# od-aws.net
KiCad netlist of a schematic drawn in EAGLE
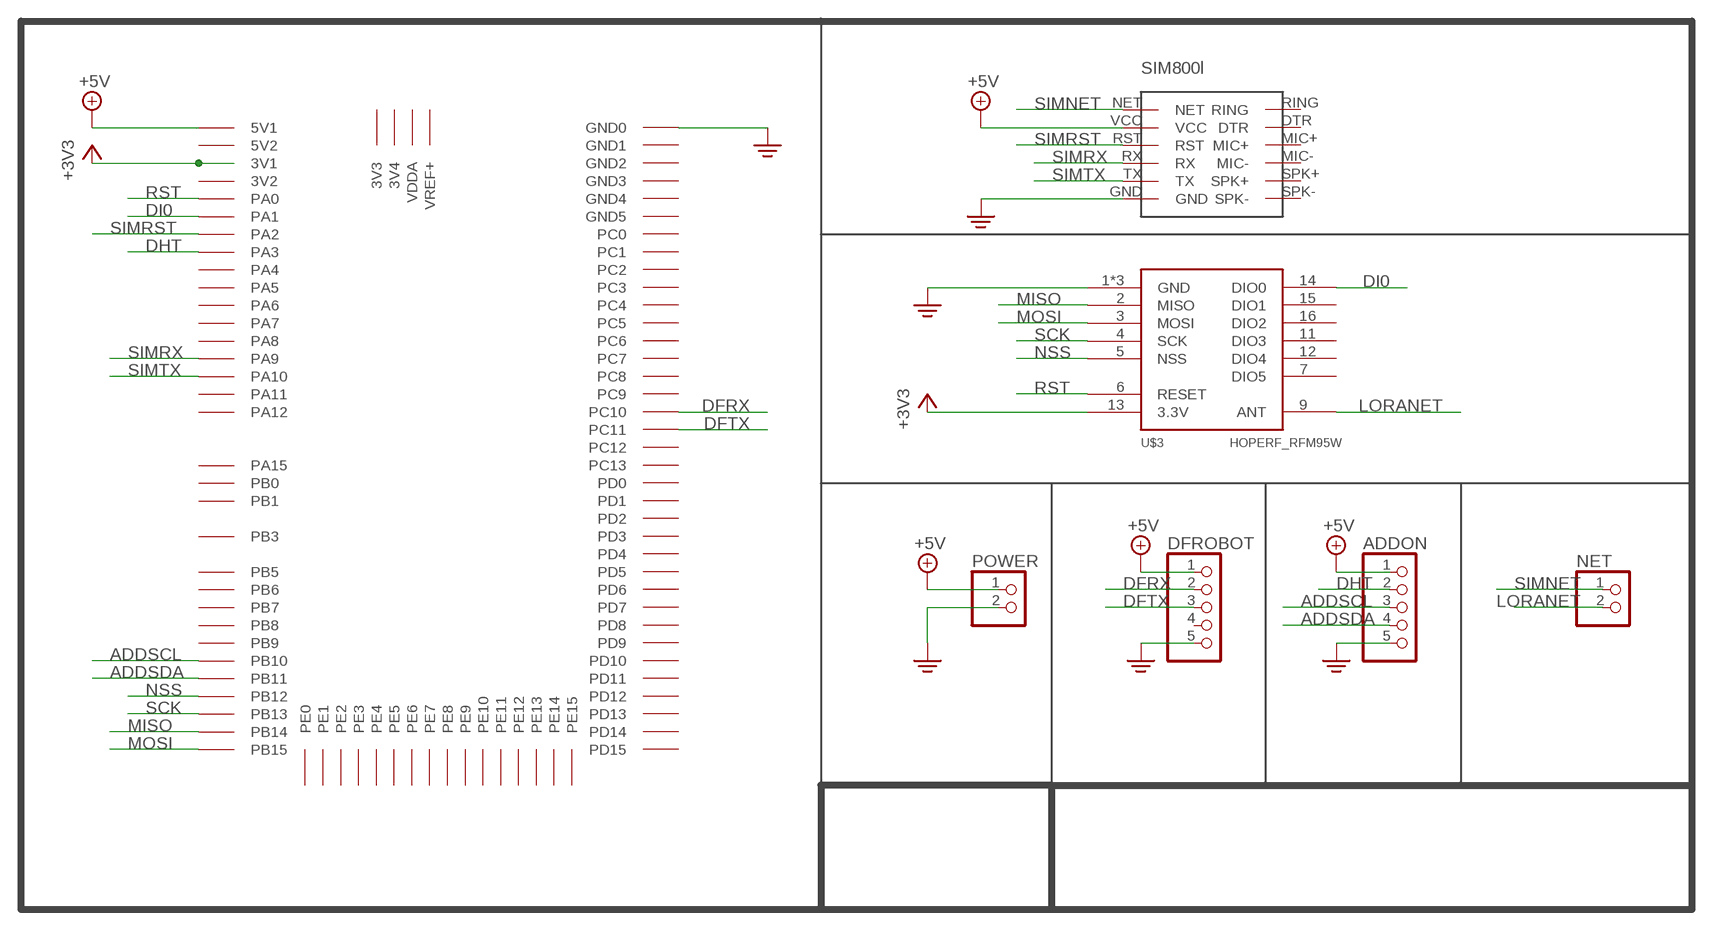
[diagram p0: schematic, sheet 1]

(export (version "E")
  (design (tool "Eeschema 10.0.6"))
  (components
    (comp (ref "ADDON")
      (value "PINHD-1X5/90")
      (footprint "eagle-import:1X05_90")
      (libsource (lib "eagle-import") (part "PINHD-1X5/90"))
    )
    (comp (ref "DFROBOT")
      (value "PINHD-1X5/90")
      (footprint "eagle-import:1X05_90")
      (libsource (lib "eagle-import") (part "PINHD-1X5/90"))
    )
    (comp (ref "NET")
      (value "PINHD-1X2/90")
      (footprint "eagle-import:1X02_90")
      (libsource (lib "eagle-import") (part "PINHD-1X2/90"))
    )
    (comp (ref "POWER")
      (value "PINHD-1X2/90")
      (footprint "eagle-import:1X02_90")
      (libsource (lib "eagle-import") (part "PINHD-1X2/90"))
    )
    (comp (ref "U$1")
      (value "STM32F407VGT6")
      (footprint "eagle-import:STM32F407VGT6")
      (libsource (lib "eagle-import") (part "STM32F407VGT6"))
    )
    (comp (ref "U$2")
      (value "SIM800L-V1")
      (footprint "eagle-import:SIM800L-V1")
      (libsource (lib "eagle-import") (part "SIM800L-V1"))
    )
    (comp (ref "U$3")
      (value "HOPERF_RFM95W")
      (footprint "eagle-import:HOPERF_RFM95W")
      (libsource (lib "eagle-import") (part "HOPERF_RFM95W"))
    )
  )
  (nets
    (net (code "1") (name "+3V3") (class "Default")
      (node (ref "U$1") (pin "3V31") (pinfunction "3V1_3V31") (pintype "bidirectional"))
      (node (ref "U$3") (pin "13") (pinfunction "3.3V_13") (pintype "power_in"))
    )
    (net (code "2") (name "+5V") (class "Default")
      (node (ref "ADDON") (pin "1") (pinfunction "1_1") (pintype "passive"))
      (node (ref "DFROBOT") (pin "1") (pinfunction "1_1") (pintype "passive"))
      (node (ref "POWER") (pin "1") (pinfunction "1_1") (pintype "passive"))
      (node (ref "U$1") (pin "5V1") (pinfunction "5V1_5V1") (pintype "bidirectional"))
      (node (ref "U$2") (pin "VCC") (pinfunction "VCC_VCC") (pintype "bidirectional"))
    )
    (net (code "3") (name "/ADDSCL") (class "Default")
      (node (ref "ADDON") (pin "3") (pinfunction "3_3") (pintype "passive"))
      (node (ref "U$1") (pin "PB10") (pinfunction "PB10_PB10") (pintype "bidirectional"))
    )
    (net (code "4") (name "/ADDSDA") (class "Default")
      (node (ref "ADDON") (pin "4") (pinfunction "4_4") (pintype "passive"))
      (node (ref "U$1") (pin "PB11") (pinfunction "PB11_PB11") (pintype "bidirectional"))
    )
    (net (code "5") (name "/DFRX") (class "Default")
      (node (ref "DFROBOT") (pin "2") (pinfunction "2_2") (pintype "passive"))
      (node (ref "U$1") (pin "PC10") (pinfunction "PC10_PC10") (pintype "bidirectional"))
    )
    (net (code "6") (name "/DFTX") (class "Default")
      (node (ref "DFROBOT") (pin "3") (pinfunction "3_3") (pintype "passive"))
      (node (ref "U$1") (pin "PC11") (pinfunction "PC11_PC11") (pintype "bidirectional"))
    )
    (net (code "7") (name "/DHT") (class "Default")
      (node (ref "ADDON") (pin "2") (pinfunction "2_2") (pintype "passive"))
      (node (ref "U$1") (pin "PA3") (pinfunction "PA3_PA3") (pintype "bidirectional"))
    )
    (net (code "8") (name "/DI0") (class "Default")
      (node (ref "U$1") (pin "PA1") (pinfunction "PA1_PA1") (pintype "bidirectional"))
      (node (ref "U$3") (pin "14") (pinfunction "DIO0_14") (pintype "bidirectional"))
    )
    (net (code "9") (name "/LORANET") (class "Default")
      (node (ref "NET") (pin "2") (pinfunction "2_2") (pintype "passive"))
      (node (ref "U$3") (pin "9") (pinfunction "ANT_9") (pintype "bidirectional"))
    )
    (net (code "10") (name "/MISO") (class "Default")
      (node (ref "U$1") (pin "PB14") (pinfunction "PB14_PB14") (pintype "bidirectional"))
      (node (ref "U$3") (pin "2") (pinfunction "MISO_2") (pintype "input"))
    )
    (net (code "11") (name "/MOSI") (class "Default")
      (node (ref "U$1") (pin "PB15") (pinfunction "PB15_PB15") (pintype "bidirectional"))
      (node (ref "U$3") (pin "3") (pinfunction "MOSI_3") (pintype "output"))
    )
    (net (code "12") (name "/NSS") (class "Default")
      (node (ref "U$1") (pin "PB12") (pinfunction "PB12_PB12") (pintype "bidirectional"))
      (node (ref "U$3") (pin "5") (pinfunction "NSS_5") (pintype "input"))
    )
    (net (code "13") (name "/RST") (class "Default")
      (node (ref "U$1") (pin "PA0") (pinfunction "PA0_PA0") (pintype "bidirectional"))
      (node (ref "U$3") (pin "6") (pinfunction "RESET_6") (pintype "bidirectional"))
    )
    (net (code "14") (name "/SCK") (class "Default")
      (node (ref "U$1") (pin "PB13") (pinfunction "PB13_PB13") (pintype "bidirectional"))
      (node (ref "U$3") (pin "4") (pinfunction "SCK_4") (pintype "input"))
    )
    (net (code "15") (name "/SIMNET") (class "Default")
      (node (ref "NET") (pin "1") (pinfunction "1_1") (pintype "passive"))
      (node (ref "U$2") (pin "NET") (pinfunction "NET_NET") (pintype "bidirectional"))
    )
    (net (code "16") (name "/SIMRST") (class "Default")
      (node (ref "U$1") (pin "PA2") (pinfunction "PA2_PA2") (pintype "bidirectional"))
      (node (ref "U$2") (pin "RST") (pinfunction "RST_RST") (pintype "bidirectional"))
    )
    (net (code "17") (name "/SIMRX") (class "Default")
      (node (ref "U$1") (pin "PA9") (pinfunction "PA9_PA9") (pintype "bidirectional"))
      (node (ref "U$2") (pin "RX") (pinfunction "RX_RX") (pintype "bidirectional"))
    )
    (net (code "18") (name "/SIMTX") (class "Default")
      (node (ref "U$1") (pin "PA10") (pinfunction "PA10_PA10") (pintype "bidirectional"))
      (node (ref "U$2") (pin "TX") (pinfunction "TX_TX") (pintype "bidirectional"))
    )
    (net (code "19") (name "PE") (class "Default")
      (node (ref "ADDON") (pin "5") (pinfunction "5_5") (pintype "passive"))
      (node (ref "DFROBOT") (pin "5") (pinfunction "5_5") (pintype "passive"))
      (node (ref "POWER") (pin "2") (pinfunction "2_2") (pintype "passive"))
      (node (ref "U$1") (pin "GND1") (pinfunction "GND0_GND1") (pintype "bidirectional"))
      (node (ref "U$2") (pin "GND") (pinfunction "GND_GND") (pintype "bidirectional"))
      (node (ref "U$3") (pin "1") (pinfunction "GND_1") (pintype "power_in"))
      (node (ref "U$3") (pin "10") (pinfunction "GND_10") (pintype "power_in"))
      (node (ref "U$3") (pin "8") (pinfunction "GND_8") (pintype "power_in"))
    )
    (net (code "20") (name "unconnected-(DFROBOT-Pad4)") (class "Default")
      (node (ref "DFROBOT") (pin "4") (pinfunction "4_4") (pintype "passive"))
    )
    (net (code "21") (name "unconnected-(U$1-3V2-Pad3V32)") (class "Default")
      (node (ref "U$1") (pin "3V32") (pinfunction "3V2_3V32") (pintype "bidirectional"))
    )
    (net (code "22") (name "unconnected-(U$1-3V3-Pad3V33)") (class "Default")
      (node (ref "U$1") (pin "3V33") (pinfunction "3V3_3V33") (pintype "bidirectional"))
    )
    (net (code "23") (name "unconnected-(U$1-3V4-Pad3V34)") (class "Default")
      (node (ref "U$1") (pin "3V34") (pinfunction "3V4_3V34") (pintype "bidirectional"))
    )
    (net (code "24") (name "unconnected-(U$1-GND1-PadGND2)") (class "Default")
      (node (ref "U$1") (pin "GND2") (pinfunction "GND1_GND2") (pintype "bidirectional"))
    )
    (net (code "25") (name "unconnected-(U$1-GND2-PadGND3)") (class "Default")
      (node (ref "U$1") (pin "GND3") (pinfunction "GND2_GND3") (pintype "bidirectional"))
    )
    (net (code "26") (name "unconnected-(U$1-GND3-PadGND4)") (class "Default")
      (node (ref "U$1") (pin "GND4") (pinfunction "GND3_GND4") (pintype "bidirectional"))
    )
    (net (code "27") (name "unconnected-(U$1-GND4-PadGND5)") (class "Default")
      (node (ref "U$1") (pin "GND5") (pinfunction "GND4_GND5") (pintype "bidirectional"))
    )
    (net (code "28") (name "unconnected-(U$1-GND5-PadGND7)") (class "Default")
      (node (ref "U$1") (pin "GND7") (pinfunction "GND5_GND7") (pintype "bidirectional"))
    )
    (net (code "29") (name "unconnected-(U$1-Pad5V2)") (class "Default")
      (node (ref "U$1") (pin "5V2") (pinfunction "5V2_5V2") (pintype "bidirectional"))
    )
    (net (code "30") (name "unconnected-(U$1-PadPA4)") (class "Default")
      (node (ref "U$1") (pin "PA4") (pinfunction "PA4_PA4") (pintype "bidirectional"))
    )
    (net (code "31") (name "unconnected-(U$1-PadPA5)") (class "Default")
      (node (ref "U$1") (pin "PA5") (pinfunction "PA5_PA5") (pintype "bidirectional"))
    )
    (net (code "32") (name "unconnected-(U$1-PadPA6)") (class "Default")
      (node (ref "U$1") (pin "PA6") (pinfunction "PA6_PA6") (pintype "bidirectional"))
    )
    (net (code "33") (name "unconnected-(U$1-PadPA7)") (class "Default")
      (node (ref "U$1") (pin "PA7") (pinfunction "PA7_PA7") (pintype "bidirectional"))
    )
    (net (code "34") (name "unconnected-(U$1-PadPA8)") (class "Default")
      (node (ref "U$1") (pin "PA8") (pinfunction "PA8_PA8") (pintype "bidirectional"))
    )
    (net (code "35") (name "unconnected-(U$1-PadPA11)") (class "Default")
      (node (ref "U$1") (pin "PA11") (pinfunction "PA11_PA11") (pintype "bidirectional"))
    )
    (net (code "36") (name "unconnected-(U$1-PadPA12)") (class "Default")
      (node (ref "U$1") (pin "PA12") (pinfunction "PA12_PA12") (pintype "bidirectional"))
    )
    (net (code "37") (name "unconnected-(U$1-PadPA15)") (class "Default")
      (node (ref "U$1") (pin "PA15") (pinfunction "PA15_PA15") (pintype "bidirectional"))
    )
    (net (code "38") (name "unconnected-(U$1-PadPB0)") (class "Default")
      (node (ref "U$1") (pin "PB0") (pinfunction "PB0_PB0") (pintype "bidirectional"))
    )
    (net (code "39") (name "unconnected-(U$1-PadPB1)") (class "Default")
      (node (ref "U$1") (pin "PB1") (pinfunction "PB1_PB1") (pintype "bidirectional"))
    )
    (net (code "40") (name "unconnected-(U$1-PadPB3)") (class "Default")
      (node (ref "U$1") (pin "PB3") (pinfunction "PB3_PB3") (pintype "bidirectional"))
    )
    (net (code "41") (name "unconnected-(U$1-PadPB5)") (class "Default")
      (node (ref "U$1") (pin "PB5") (pinfunction "PB5_PB5") (pintype "bidirectional"))
    )
    (net (code "42") (name "unconnected-(U$1-PadPB6)") (class "Default")
      (node (ref "U$1") (pin "PB6") (pinfunction "PB6_PB6") (pintype "bidirectional"))
    )
    (net (code "43") (name "unconnected-(U$1-PadPB7)") (class "Default")
      (node (ref "U$1") (pin "PB7") (pinfunction "PB7_PB7") (pintype "bidirectional"))
    )
    (net (code "44") (name "unconnected-(U$1-PadPB8)") (class "Default")
      (node (ref "U$1") (pin "PB8") (pinfunction "PB8_PB8") (pintype "bidirectional"))
    )
    (net (code "45") (name "unconnected-(U$1-PadPB9)") (class "Default")
      (node (ref "U$1") (pin "PB9") (pinfunction "PB9_PB9") (pintype "bidirectional"))
    )
    (net (code "46") (name "unconnected-(U$1-PadPC0)") (class "Default")
      (node (ref "U$1") (pin "PC0") (pinfunction "PC0_PC0") (pintype "bidirectional"))
    )
    (net (code "47") (name "unconnected-(U$1-PadPC1)") (class "Default")
      (node (ref "U$1") (pin "PC1") (pinfunction "PC1_PC1") (pintype "bidirectional"))
    )
    (net (code "48") (name "unconnected-(U$1-PadPC2)") (class "Default")
      (node (ref "U$1") (pin "PC2") (pinfunction "PC2_PC2") (pintype "bidirectional"))
    )
    (net (code "49") (name "unconnected-(U$1-PadPC3)") (class "Default")
      (node (ref "U$1") (pin "PC3") (pinfunction "PC3_PC3") (pintype "bidirectional"))
    )
    (net (code "50") (name "unconnected-(U$1-PadPC4)") (class "Default")
      (node (ref "U$1") (pin "PC4") (pinfunction "PC4_PC4") (pintype "bidirectional"))
    )
    (net (code "51") (name "unconnected-(U$1-PadPC5)") (class "Default")
      (node (ref "U$1") (pin "PC5") (pinfunction "PC5_PC5") (pintype "bidirectional"))
    )
    (net (code "52") (name "unconnected-(U$1-PadPC6)") (class "Default")
      (node (ref "U$1") (pin "PC6") (pinfunction "PC6_PC6") (pintype "bidirectional"))
    )
    (net (code "53") (name "unconnected-(U$1-PadPC7)") (class "Default")
      (node (ref "U$1") (pin "PC7") (pinfunction "PC7_PC7") (pintype "bidirectional"))
    )
    (net (code "54") (name "unconnected-(U$1-PadPC8)") (class "Default")
      (node (ref "U$1") (pin "PC8") (pinfunction "PC8_PC8") (pintype "bidirectional"))
    )
    (net (code "55") (name "unconnected-(U$1-PadPC9)") (class "Default")
      (node (ref "U$1") (pin "PC9") (pinfunction "PC9_PC9") (pintype "bidirectional"))
    )
    (net (code "56") (name "unconnected-(U$1-PadPC12)") (class "Default")
      (node (ref "U$1") (pin "PC12") (pinfunction "PC12_PC12") (pintype "bidirectional"))
    )
    (net (code "57") (name "unconnected-(U$1-PadPC13)") (class "Default")
      (node (ref "U$1") (pin "PC13") (pinfunction "PC13_PC13") (pintype "bidirectional"))
    )
    (net (code "58") (name "unconnected-(U$1-PadPD0)") (class "Default")
      (node (ref "U$1") (pin "PD0") (pinfunction "PD0_PD0") (pintype "bidirectional"))
    )
    (net (code "59") (name "unconnected-(U$1-PadPD1)") (class "Default")
      (node (ref "U$1") (pin "PD1") (pinfunction "PD1_PD1") (pintype "bidirectional"))
    )
    (net (code "60") (name "unconnected-(U$1-PadPD2)") (class "Default")
      (node (ref "U$1") (pin "PD2") (pinfunction "PD2_PD2") (pintype "bidirectional"))
    )
    (net (code "61") (name "unconnected-(U$1-PadPD3)") (class "Default")
      (node (ref "U$1") (pin "PD3") (pinfunction "PD3_PD3") (pintype "bidirectional"))
    )
    (net (code "62") (name "unconnected-(U$1-PadPD4)") (class "Default")
      (node (ref "U$1") (pin "PD4") (pinfunction "PD4_PD4") (pintype "bidirectional"))
    )
    (net (code "63") (name "unconnected-(U$1-PadPD5)") (class "Default")
      (node (ref "U$1") (pin "PD5") (pinfunction "PD5_PD5") (pintype "bidirectional"))
    )
    (net (code "64") (name "unconnected-(U$1-PadPD6)") (class "Default")
      (node (ref "U$1") (pin "PD6") (pinfunction "PD6_PD6") (pintype "bidirectional"))
    )
    (net (code "65") (name "unconnected-(U$1-PadPD7)") (class "Default")
      (node (ref "U$1") (pin "PD7") (pinfunction "PD7_PD7") (pintype "bidirectional"))
    )
    (net (code "66") (name "unconnected-(U$1-PadPD8)") (class "Default")
      (node (ref "U$1") (pin "PD8") (pinfunction "PD8_PD8") (pintype "bidirectional"))
    )
    (net (code "67") (name "unconnected-(U$1-PadPD9)") (class "Default")
      (node (ref "U$1") (pin "PD9") (pinfunction "PD9_PD9") (pintype "bidirectional"))
    )
    (net (code "68") (name "unconnected-(U$1-PadPD10)") (class "Default")
      (node (ref "U$1") (pin "PD10") (pinfunction "PD10_PD10") (pintype "bidirectional"))
    )
    (net (code "69") (name "unconnected-(U$1-PadPD11)") (class "Default")
      (node (ref "U$1") (pin "PD11") (pinfunction "PD11_PD11") (pintype "bidirectional"))
    )
    (net (code "70") (name "unconnected-(U$1-PadPD12)") (class "Default")
      (node (ref "U$1") (pin "PD12") (pinfunction "PD12_PD12") (pintype "bidirectional"))
    )
    (net (code "71") (name "unconnected-(U$1-PadPD13)") (class "Default")
      (node (ref "U$1") (pin "PD13") (pinfunction "PD13_PD13") (pintype "bidirectional"))
    )
    (net (code "72") (name "unconnected-(U$1-PadPD14)") (class "Default")
      (node (ref "U$1") (pin "PD14") (pinfunction "PD14_PD14") (pintype "bidirectional"))
    )
    (net (code "73") (name "unconnected-(U$1-PadPD15)") (class "Default")
      (node (ref "U$1") (pin "PD15") (pinfunction "PD15_PD15") (pintype "bidirectional"))
    )
    (net (code "74") (name "unconnected-(U$1-PadPE0)") (class "Default")
      (node (ref "U$1") (pin "PE0") (pinfunction "PE0_PE0") (pintype "bidirectional"))
    )
    (net (code "75") (name "unconnected-(U$1-PadPE1)") (class "Default")
      (node (ref "U$1") (pin "PE1") (pinfunction "PE1_PE1") (pintype "bidirectional"))
    )
    (net (code "76") (name "unconnected-(U$1-PadPE2)") (class "Default")
      (node (ref "U$1") (pin "PE2") (pinfunction "PE2_PE2") (pintype "bidirectional"))
    )
    (net (code "77") (name "unconnected-(U$1-PadPE3)") (class "Default")
      (node (ref "U$1") (pin "PE3") (pinfunction "PE3_PE3") (pintype "bidirectional"))
    )
    (net (code "78") (name "unconnected-(U$1-PadPE4)") (class "Default")
      (node (ref "U$1") (pin "PE4") (pinfunction "PE4_PE4") (pintype "bidirectional"))
    )
    (net (code "79") (name "unconnected-(U$1-PadPE5)") (class "Default")
      (node (ref "U$1") (pin "PE5") (pinfunction "PE5_PE5") (pintype "bidirectional"))
    )
    (net (code "80") (name "unconnected-(U$1-PadPE6)") (class "Default")
      (node (ref "U$1") (pin "PE6") (pinfunction "PE6_PE6") (pintype "bidirectional"))
    )
    (net (code "81") (name "unconnected-(U$1-PadPE7)") (class "Default")
      (node (ref "U$1") (pin "PE7") (pinfunction "PE7_PE7") (pintype "bidirectional"))
    )
    (net (code "82") (name "unconnected-(U$1-PadPE8)") (class "Default")
      (node (ref "U$1") (pin "PE8") (pinfunction "PE8_PE8") (pintype "bidirectional"))
    )
    (net (code "83") (name "unconnected-(U$1-PadPE9)") (class "Default")
      (node (ref "U$1") (pin "PE9") (pinfunction "PE9_PE9") (pintype "bidirectional"))
    )
    (net (code "84") (name "unconnected-(U$1-PadPE10)") (class "Default")
      (node (ref "U$1") (pin "PE10") (pinfunction "PE10_PE10") (pintype "bidirectional"))
    )
    (net (code "85") (name "unconnected-(U$1-PadPE11)") (class "Default")
      (node (ref "U$1") (pin "PE11") (pinfunction "PE11_PE11") (pintype "bidirectional"))
    )
    (net (code "86") (name "unconnected-(U$1-PadPE12)") (class "Default")
      (node (ref "U$1") (pin "PE12") (pinfunction "PE12_PE12") (pintype "bidirectional"))
    )
    (net (code "87") (name "unconnected-(U$1-PadPE13)") (class "Default")
      (node (ref "U$1") (pin "PE13") (pinfunction "PE13_PE13") (pintype "bidirectional"))
    )
    (net (code "88") (name "unconnected-(U$1-PadPE14)") (class "Default")
      (node (ref "U$1") (pin "PE14") (pinfunction "PE14_PE14") (pintype "bidirectional"))
    )
    (net (code "89") (name "unconnected-(U$1-PadPE15)") (class "Default")
      (node (ref "U$1") (pin "PE15") (pinfunction "PE15_PE15") (pintype "bidirectional"))
    )
    (net (code "90") (name "unconnected-(U$1-PadVDDA)") (class "Default")
      (node (ref "U$1") (pin "VDDA") (pinfunction "VDDA_VDDA") (pintype "bidirectional"))
    )
    (net (code "91") (name "unconnected-(U$1-PadVREF+)") (class "Default")
      (node (ref "U$1") (pin "VREF+") (pinfunction "VREF+_VREF+") (pintype "bidirectional"))
    )
    (net (code "92") (name "unconnected-(U$2-PadDTR)") (class "Default")
      (node (ref "U$2") (pin "DTR") (pinfunction "DTR_DTR") (pintype "bidirectional"))
    )
    (net (code "93") (name "unconnected-(U$2-PadMIC+)") (class "Default")
      (node (ref "U$2") (pin "MIC+") (pinfunction "MIC+_MIC+") (pintype "bidirectional"))
    )
    (net (code "94") (name "unconnected-(U$2-PadMIC-)") (class "Default")
      (node (ref "U$2") (pin "MIC-") (pinfunction "MIC-_MIC-") (pintype "bidirectional"))
    )
    (net (code "95") (name "unconnected-(U$2-PadRING)") (class "Default")
      (node (ref "U$2") (pin "RING") (pinfunction "RING_RING") (pintype "bidirectional"))
    )
    (net (code "96") (name "unconnected-(U$2-PadSPK+)") (class "Default")
      (node (ref "U$2") (pin "SPK+") (pinfunction "SPK+_SPK+") (pintype "bidirectional"))
    )
    (net (code "97") (name "unconnected-(U$2-PadSPK-)") (class "Default")
      (node (ref "U$2") (pin "SPK-") (pinfunction "SPK-_SPK-") (pintype "bidirectional"))
    )
    (net (code "98") (name "unconnected-(U$3-DIO1-Pad15)") (class "Default")
      (node (ref "U$3") (pin "15") (pinfunction "DIO1_15") (pintype "bidirectional"))
    )
    (net (code "99") (name "unconnected-(U$3-DIO2-Pad16)") (class "Default")
      (node (ref "U$3") (pin "16") (pinfunction "DIO2_16") (pintype "bidirectional"))
    )
    (net (code "100") (name "unconnected-(U$3-DIO3-Pad11)") (class "Default")
      (node (ref "U$3") (pin "11") (pinfunction "DIO3_11") (pintype "bidirectional"))
    )
    (net (code "101") (name "unconnected-(U$3-DIO4-Pad12)") (class "Default")
      (node (ref "U$3") (pin "12") (pinfunction "DIO4_12") (pintype "bidirectional"))
    )
    (net (code "102") (name "unconnected-(U$3-DIO5-Pad7)") (class "Default")
      (node (ref "U$3") (pin "7") (pinfunction "DIO5_7") (pintype "bidirectional"))
    )
  )
)
